# Comparador_LM339.net
KiCad netlist of a schematic drawn in EAGLE
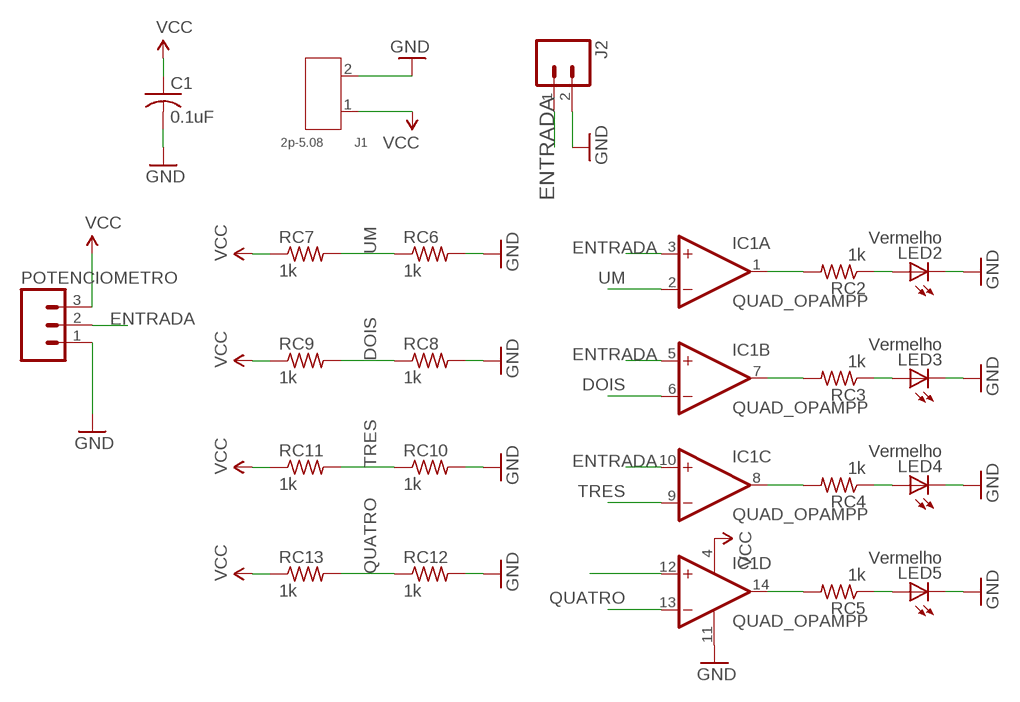
[diagram p0: schematic, sheet 1]

(export (version "E")
  (design (tool "Eeschema 10.0.6"))
  (components
    (comp (ref "C1")
      (value "0.1uF")
      (footprint "eagle-import:C050-024X044")
      (libsource (lib "eagle-import") (part "C-US050-024X044"))
    )
    (comp (ref "IC1")
      (value "QUAD_OPAMPP")
      (footprint "eagle-import:DIL14")
      (libsource (lib "eagle-import") (part "QUAD_OPAMPP"))
    )
    (comp (ref "J1")
      (value "2p-5.08")
      (footprint "eagle-import:H2-5.0-10.5X8.0MM")
      (fields (field (name "MPN") "GS009S-2P-2"))
      (libsource (lib "eagle-import") (part "DIP-BLUE-SCREW-TERMINAL(2P-5.08)"))
    )
    (comp (ref "J2")
      (value "M02PTH")
      (footprint "eagle-import:1X02")
      (libsource (lib "eagle-import") (part "M02PTH"))
    )
    (comp (ref "LED2")
      (value "Vermelho")
      (footprint "eagle-import:LED5MM")
      (libsource (lib "eagle-import") (part "LED5MM"))
    )
    (comp (ref "LED3")
      (value "Vermelho")
      (footprint "eagle-import:LED5MM")
      (libsource (lib "eagle-import") (part "LED5MM"))
    )
    (comp (ref "LED4")
      (value "Vermelho")
      (footprint "eagle-import:LED5MM")
      (libsource (lib "eagle-import") (part "LED5MM"))
    )
    (comp (ref "LED5")
      (value "Vermelho")
      (footprint "eagle-import:LED5MM")
      (libsource (lib "eagle-import") (part "LED5MM"))
    )
    (comp (ref "POTENCIOMETRO")
      (value "M03-SCREW-5MM")
      (footprint "eagle-import:SCREWTERMINAL-5MM-3")
      (libsource (lib "eagle-import") (part "M03-SCREW-5MM"))
    )
    (comp (ref "RC2")
      (value "1k")
      (footprint "eagle-import:0207_10")
      (libsource (lib "eagle-import") (part "R-US_0207/10"))
    )
    (comp (ref "RC3")
      (value "1k")
      (footprint "eagle-import:0207_10")
      (libsource (lib "eagle-import") (part "R-US_0207/10"))
    )
    (comp (ref "RC4")
      (value "1k")
      (footprint "eagle-import:0207_10")
      (libsource (lib "eagle-import") (part "R-US_0207/10"))
    )
    (comp (ref "RC5")
      (value "1k")
      (footprint "eagle-import:0207_10")
      (libsource (lib "eagle-import") (part "R-US_0207/10"))
    )
    (comp (ref "RC6")
      (value "1k")
      (footprint "eagle-import:0207_10")
      (libsource (lib "eagle-import") (part "R-US_0207/10"))
    )
    (comp (ref "RC7")
      (value "1k")
      (footprint "eagle-import:0207_10")
      (libsource (lib "eagle-import") (part "R-US_0207/10"))
    )
    (comp (ref "RC8")
      (value "1k")
      (footprint "eagle-import:0207_10")
      (libsource (lib "eagle-import") (part "R-US_0207/10"))
    )
    (comp (ref "RC9")
      (value "1k")
      (footprint "eagle-import:0207_10")
      (libsource (lib "eagle-import") (part "R-US_0207/10"))
    )
    (comp (ref "RC10")
      (value "1k")
      (footprint "eagle-import:0207_10")
      (libsource (lib "eagle-import") (part "R-US_0207/10"))
    )
    (comp (ref "RC11")
      (value "1k")
      (footprint "eagle-import:0207_10")
      (libsource (lib "eagle-import") (part "R-US_0207/10"))
    )
    (comp (ref "RC12")
      (value "1k")
      (footprint "eagle-import:0207_10")
      (libsource (lib "eagle-import") (part "R-US_0207/10"))
    )
    (comp (ref "RC13")
      (value "1k")
      (footprint "eagle-import:0207_10")
      (libsource (lib "eagle-import") (part "R-US_0207/10"))
    )
  )
  (nets
    (net (code "1") (name "/DOIS") (class "Default")
      (node (ref "IC1") (pin "6") (pinfunction "-IN_6") (pintype "input"))
      (node (ref "RC8") (pin "1") (pinfunction "1_1") (pintype "passive"))
      (node (ref "RC9") (pin "2") (pinfunction "2_2") (pintype "passive"))
    )
    (net (code "2") (name "/ENTRADA") (class "Default")
      (node (ref "IC1") (pin "10") (pinfunction "+IN_10") (pintype "input"))
      (node (ref "IC1") (pin "12") (pinfunction "+IN_12") (pintype "input"))
      (node (ref "IC1") (pin "3") (pinfunction "+IN_3") (pintype "input"))
      (node (ref "IC1") (pin "5") (pinfunction "+IN_5") (pintype "input"))
      (node (ref "J2") (pin "1") (pinfunction "1_1") (pintype "passive"))
      (node (ref "POTENCIOMETRO") (pin "2") (pinfunction "2_2") (pintype "passive"))
    )
    (net (code "3") (name "/QUATRO") (class "Default")
      (node (ref "IC1") (pin "13") (pinfunction "-IN_13") (pintype "input"))
      (node (ref "RC12") (pin "1") (pinfunction "1_1") (pintype "passive"))
      (node (ref "RC13") (pin "2") (pinfunction "2_2") (pintype "passive"))
    )
    (net (code "4") (name "/TRES") (class "Default")
      (node (ref "IC1") (pin "9") (pinfunction "-IN_9") (pintype "input"))
      (node (ref "RC10") (pin "1") (pinfunction "1_1") (pintype "passive"))
      (node (ref "RC11") (pin "2") (pinfunction "2_2") (pintype "passive"))
    )
    (net (code "5") (name "/UM") (class "Default")
      (node (ref "IC1") (pin "2") (pinfunction "-IN_2") (pintype "input"))
      (node (ref "RC6") (pin "1") (pinfunction "1_1") (pintype "passive"))
      (node (ref "RC7") (pin "2") (pinfunction "2_2") (pintype "passive"))
    )
    (net (code "6") (name "GND") (class "Default")
      (node (ref "C1") (pin "2") (pinfunction "2_2") (pintype "passive"))
      (node (ref "IC1") (pin "11") (pinfunction "V-_11") (pintype "power_in"))
      (node (ref "J1") (pin "2") (pinfunction "2_2") (pintype "bidirectional"))
      (node (ref "J2") (pin "2") (pinfunction "2_2") (pintype "passive"))
      (node (ref "LED2") (pin "K") (pinfunction "C_K") (pintype "passive"))
      (node (ref "LED3") (pin "K") (pinfunction "C_K") (pintype "passive"))
      (node (ref "LED4") (pin "K") (pinfunction "C_K") (pintype "passive"))
      (node (ref "LED5") (pin "K") (pinfunction "C_K") (pintype "passive"))
      (node (ref "POTENCIOMETRO") (pin "1") (pinfunction "1_1") (pintype "passive"))
      (node (ref "RC10") (pin "2") (pinfunction "2_2") (pintype "passive"))
      (node (ref "RC12") (pin "2") (pinfunction "2_2") (pintype "passive"))
      (node (ref "RC6") (pin "2") (pinfunction "2_2") (pintype "passive"))
      (node (ref "RC8") (pin "2") (pinfunction "2_2") (pintype "passive"))
    )
    (net (code "7") (name "Net-(IC1A-OUT)") (class "Default")
      (node (ref "IC1") (pin "1") (pinfunction "OUT_1") (pintype "output"))
      (node (ref "RC2") (pin "2") (pinfunction "2_2") (pintype "passive"))
    )
    (net (code "8") (name "Net-(IC1B-OUT)") (class "Default")
      (node (ref "IC1") (pin "7") (pinfunction "OUT_7") (pintype "output"))
      (node (ref "RC3") (pin "2") (pinfunction "2_2") (pintype "passive"))
    )
    (net (code "9") (name "Net-(IC1C-OUT)") (class "Default")
      (node (ref "IC1") (pin "8") (pinfunction "OUT_8") (pintype "output"))
      (node (ref "RC4") (pin "2") (pinfunction "2_2") (pintype "passive"))
    )
    (net (code "10") (name "Net-(IC1D-OUT)") (class "Default")
      (node (ref "IC1") (pin "14") (pinfunction "OUT_14") (pintype "output"))
      (node (ref "RC5") (pin "2") (pinfunction "2_2") (pintype "passive"))
    )
    (net (code "11") (name "Net-(LED2-PadA)") (class "Default")
      (node (ref "LED2") (pin "A") (pinfunction "A_A") (pintype "passive"))
      (node (ref "RC2") (pin "1") (pinfunction "1_1") (pintype "passive"))
    )
    (net (code "12") (name "Net-(LED3-PadA)") (class "Default")
      (node (ref "LED3") (pin "A") (pinfunction "A_A") (pintype "passive"))
      (node (ref "RC3") (pin "1") (pinfunction "1_1") (pintype "passive"))
    )
    (net (code "13") (name "Net-(LED4-PadA)") (class "Default")
      (node (ref "LED4") (pin "A") (pinfunction "A_A") (pintype "passive"))
      (node (ref "RC4") (pin "1") (pinfunction "1_1") (pintype "passive"))
    )
    (net (code "14") (name "Net-(LED5-PadA)") (class "Default")
      (node (ref "LED5") (pin "A") (pinfunction "A_A") (pintype "passive"))
      (node (ref "RC5") (pin "1") (pinfunction "1_1") (pintype "passive"))
    )
    (net (code "15") (name "VCC") (class "Default")
      (node (ref "C1") (pin "1") (pinfunction "1_1") (pintype "passive"))
      (node (ref "IC1") (pin "4") (pinfunction "V+_4") (pintype "power_in"))
      (node (ref "J1") (pin "1") (pinfunction "1_1") (pintype "bidirectional"))
      (node (ref "POTENCIOMETRO") (pin "3") (pinfunction "3_3") (pintype "passive"))
      (node (ref "RC11") (pin "1") (pinfunction "1_1") (pintype "passive"))
      (node (ref "RC13") (pin "1") (pinfunction "1_1") (pintype "passive"))
      (node (ref "RC7") (pin "1") (pinfunction "1_1") (pintype "passive"))
      (node (ref "RC9") (pin "1") (pinfunction "1_1") (pintype "passive"))
    )
  )
)
